# sirius1.net
KiCad netlist of a schematic drawn in EAGLE
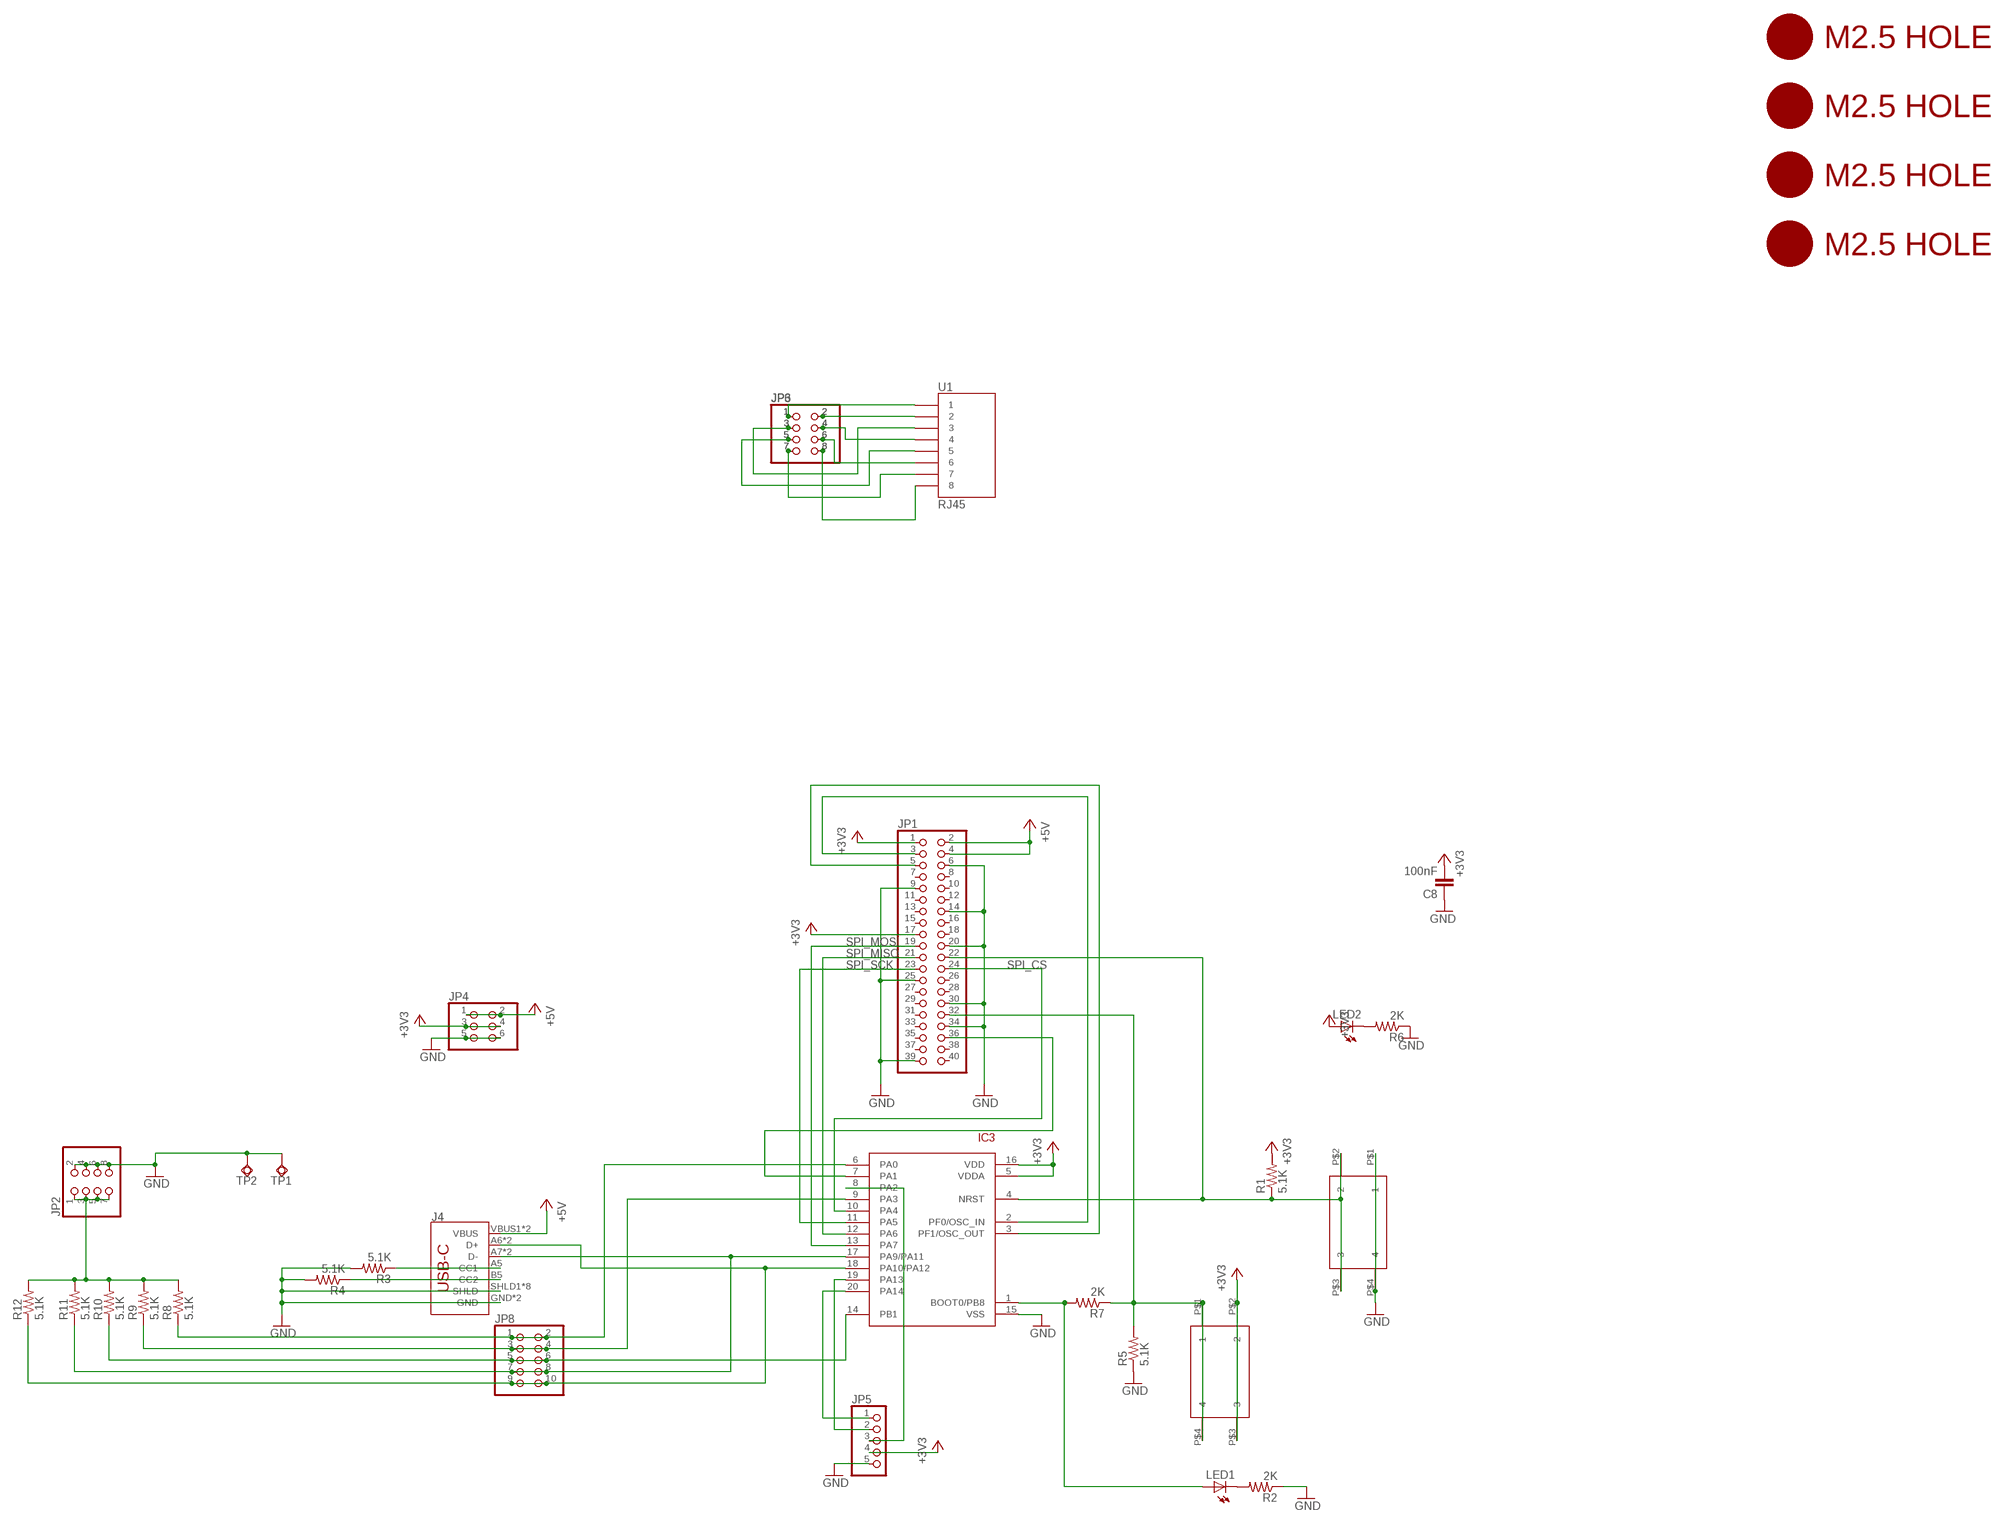
[diagram p0: schematic, sheet 1]

(export (version "E")
  (design (tool "Eeschema 10.0.6"))
  (components
    (comp (ref "C8")
      (value "100nF")
      (footprint "eagle-import:0805@1")
      (libsource (lib "eagle-import") (part "CAP0805"))
    )
    (comp (ref "IC3")
      (value "STM32F042F4")
      (footprint "eagle-import:TSSOP20")
      (libsource (lib "eagle-import") (part "STM32F042F4"))
    )
    (comp (ref "J4")
      (value "USB_C16PIN")
      (footprint "eagle-import:USB-C-16P")
      (libsource (lib "eagle-import") (part "USB_C16PIN"))
    )
    (comp (ref "JP1")
      (value "PINHD-2X20-BIG")
      (footprint "eagle-import:2X20-BIG")
      (libsource (lib "eagle-import") (part "PINHD-2X20-BIG"))
    )
    (comp (ref "JP2")
      (value "PINHD-2X4")
      (footprint "eagle-import:2X04")
      (libsource (lib "eagle-import") (part "PINHD-2X4"))
    )
    (comp (ref "JP3")
      (value "PINHD-2X4")
      (footprint "eagle-import:2X04")
      (libsource (lib "eagle-import") (part "PINHD-2X4"))
    )
    (comp (ref "JP4")
      (value "PINHD-2X3")
      (footprint "eagle-import:2X03")
      (libsource (lib "eagle-import") (part "PINHD-2X3"))
    )
    (comp (ref "JP5")
      (value "PINHD-1X5")
      (footprint "eagle-import:1X05")
      (libsource (lib "eagle-import") (part "PINHD-1X5"))
    )
    (comp (ref "JP6")
      (value "PINHD-2X4")
      (footprint "eagle-import:2X04")
      (libsource (lib "eagle-import") (part "PINHD-2X4"))
    )
    (comp (ref "JP8")
      (value "PINHD-2X5")
      (footprint "eagle-import:2X05")
      (libsource (lib "eagle-import") (part "PINHD-2X5"))
    )
    (comp (ref "LED1")
      (value "LEDCHIP-LED0805")
      (footprint "eagle-import:CHIP-LED0805")
      (libsource (lib "eagle-import") (part "LEDCHIP-LED0805"))
    )
    (comp (ref "LED2")
      (value "LEDCHIP-LED0805")
      (footprint "eagle-import:CHIP-LED0805")
      (libsource (lib "eagle-import") (part "LEDCHIP-LED0805"))
    )
    (comp (ref "R1")
      (value "5.1K")
      (footprint "eagle-import:0805")
      (libsource (lib "eagle-import") (part "RESISTOR0805-RES"))
    )
    (comp (ref "R2")
      (value "2K")
      (footprint "eagle-import:0805")
      (libsource (lib "eagle-import") (part "RESISTOR0805-RES"))
    )
    (comp (ref "R3")
      (value "5.1K")
      (footprint "eagle-import:0805")
      (libsource (lib "eagle-import") (part "RESISTOR0805-RES"))
    )
    (comp (ref "R4")
      (value "5.1K")
      (footprint "eagle-import:0805")
      (libsource (lib "eagle-import") (part "RESISTOR0805-RES"))
    )
    (comp (ref "R5")
      (value "5.1K")
      (footprint "eagle-import:0805")
      (libsource (lib "eagle-import") (part "RESISTOR0805-RES"))
    )
    (comp (ref "R6")
      (value "2K")
      (footprint "eagle-import:0805")
      (libsource (lib "eagle-import") (part "RESISTOR0805-RES"))
    )
    (comp (ref "R7")
      (value "2K")
      (footprint "eagle-import:0805")
      (libsource (lib "eagle-import") (part "RESISTOR0805-RES"))
    )
    (comp (ref "R8")
      (value "5.1K")
      (footprint "eagle-import:0805")
      (libsource (lib "eagle-import") (part "RESISTOR0805-RES"))
    )
    (comp (ref "R9")
      (value "5.1K")
      (footprint "eagle-import:0805")
      (libsource (lib "eagle-import") (part "RESISTOR0805-RES"))
    )
    (comp (ref "R10")
      (value "5.1K")
      (footprint "eagle-import:0805")
      (libsource (lib "eagle-import") (part "RESISTOR0805-RES"))
    )
    (comp (ref "R11")
      (value "5.1K")
      (footprint "eagle-import:0805")
      (libsource (lib "eagle-import") (part "RESISTOR0805-RES"))
    )
    (comp (ref "R12")
      (value "5.1K")
      (footprint "eagle-import:0805")
      (libsource (lib "eagle-import") (part "RESISTOR0805-RES"))
    )
    (comp (ref "SW1")
      (value "324_SW")
      (footprint "eagle-import:342_SWICH_FOOT")
      (libsource (lib "eagle-import") (part "324_SW"))
    )
    (comp (ref "SW4")
      (value "324_SW")
      (footprint "eagle-import:342_SWICH_FOOT")
      (libsource (lib "eagle-import") (part "324_SW"))
    )
    (comp (ref "TP1")
      (value "TPSQPAD1-20")
      (footprint "eagle-import:P1-20")
      (libsource (lib "eagle-import") (part "TPSQPAD1-20"))
    )
    (comp (ref "TP2")
      (value "TPSQPAD1-20")
      (footprint "eagle-import:P1-20")
      (libsource (lib "eagle-import") (part "TPSQPAD1-20"))
    )
    (comp (ref "U$2")
      (value "M2.5HOLE")
      (footprint "eagle-import:M2.5HOLE")
      (libsource (lib "eagle-import") (part "M2.5HOLE"))
    )
    (comp (ref "U$3")
      (value "M2.5HOLE")
      (footprint "eagle-import:M2.5HOLE")
      (libsource (lib "eagle-import") (part "M2.5HOLE"))
    )
    (comp (ref "U$4")
      (value "M2.5HOLE")
      (footprint "eagle-import:M2.5HOLE")
      (libsource (lib "eagle-import") (part "M2.5HOLE"))
    )
    (comp (ref "U$5")
      (value "M2.5HOLE")
      (footprint "eagle-import:M2.5HOLE")
      (libsource (lib "eagle-import") (part "M2.5HOLE"))
    )
    (comp (ref "U1")
      (value "RJ45")
      (footprint "eagle-import:RJ45-8")
      (libsource (lib "eagle-import") (part "RJ45-8PTH"))
    )
  )
  (nets
    (net (code "1") (name "+3V3") (class "Default")
      (node (ref "C8") (pin "2") (pinfunction "2_2") (pintype "passive"))
      (node (ref "IC3") (pin "16") (pinfunction "VDD_16") (pintype "bidirectional"))
      (node (ref "IC3") (pin "5") (pinfunction "VDDA_5") (pintype "bidirectional"))
      (node (ref "JP1") (pin "1") (pinfunction "1_1") (pintype "passive"))
      (node (ref "JP1") (pin "17") (pinfunction "17_17") (pintype "passive"))
      (node (ref "JP4") (pin "3") (pinfunction "3_3") (pintype "passive"))
      (node (ref "JP4") (pin "4") (pinfunction "4_4") (pintype "passive"))
      (node (ref "JP5") (pin "4") (pinfunction "4_4") (pintype "passive"))
      (node (ref "LED2") (pin "A") (pinfunction "A_A") (pintype "passive"))
      (node (ref "R1") (pin "2") (pinfunction "2_2") (pintype "passive"))
      (node (ref "SW1") (pin "P$2") (pinfunction "2_P$2") (pintype "bidirectional"))
      (node (ref "SW1") (pin "P$3") (pinfunction "3_P$3") (pintype "bidirectional"))
    )
    (net (code "2") (name "+5V") (class "Default")
      (node (ref "J4") (pin "VBUS1") (pinfunction "VBUS_VBUS1") (pintype "bidirectional"))
      (node (ref "J4") (pin "VBUS2") (pinfunction "VBUS_VBUS2") (pintype "bidirectional"))
      (node (ref "JP1") (pin "2") (pinfunction "2_2") (pintype "passive"))
      (node (ref "JP1") (pin "4") (pinfunction "4_4") (pintype "passive"))
      (node (ref "JP4") (pin "1") (pinfunction "1_1") (pintype "passive"))
      (node (ref "JP4") (pin "2") (pinfunction "2_2") (pintype "passive"))
    )
    (net (code "3") (name "/SPI_CS") (class "Default")
      (node (ref "IC3") (pin "10") (pinfunction "PA4_10") (pintype "bidirectional"))
      (node (ref "JP1") (pin "24") (pinfunction "24_24") (pintype "passive"))
    )
    (net (code "4") (name "/SPI_MISO") (class "Default")
      (node (ref "IC3") (pin "12") (pinfunction "PA6_12") (pintype "bidirectional"))
      (node (ref "JP1") (pin "21") (pinfunction "21_21") (pintype "passive"))
    )
    (net (code "5") (name "/SPI_MOSI") (class "Default")
      (node (ref "IC3") (pin "13") (pinfunction "PA7_13") (pintype "bidirectional"))
      (node (ref "JP1") (pin "19") (pinfunction "19_19") (pintype "passive"))
    )
    (net (code "6") (name "/SPI_SCK") (class "Default")
      (node (ref "IC3") (pin "11") (pinfunction "PA5_11") (pintype "bidirectional"))
      (node (ref "JP1") (pin "23") (pinfunction "23_23") (pintype "passive"))
    )
    (net (code "7") (name "GND") (class "Default")
      (node (ref "C8") (pin "1") (pinfunction "1_1") (pintype "passive"))
      (node (ref "IC3") (pin "15") (pinfunction "VSS_15") (pintype "bidirectional"))
      (node (ref "J4") (pin "GND") (pinfunction "GND_GND") (pintype "bidirectional"))
      (node (ref "J4") (pin "GND2") (pinfunction "GND_GND2") (pintype "bidirectional"))
      (node (ref "J4") (pin "SHLD1") (pinfunction "SHLD_SHLD1") (pintype "bidirectional"))
      (node (ref "J4") (pin "SHLD2") (pinfunction "SHLD_SHLD2") (pintype "bidirectional"))
      (node (ref "J4") (pin "SHLD3") (pinfunction "SHLD_SHLD3") (pintype "bidirectional"))
      (node (ref "J4") (pin "SHLD4") (pinfunction "SHLD_SHLD4") (pintype "bidirectional"))
      (node (ref "J4") (pin "SHLD5") (pinfunction "SHLD_SHLD5") (pintype "bidirectional"))
      (node (ref "J4") (pin "SHLD6") (pinfunction "SHLD_SHLD6") (pintype "bidirectional"))
      (node (ref "J4") (pin "SHLD7") (pinfunction "SHLD_SHLD7") (pintype "bidirectional"))
      (node (ref "J4") (pin "SHLD8") (pinfunction "SHLD_SHLD8") (pintype "bidirectional"))
      (node (ref "JP1") (pin "14") (pinfunction "14_14") (pintype "passive"))
      (node (ref "JP1") (pin "20") (pinfunction "20_20") (pintype "passive"))
      (node (ref "JP1") (pin "25") (pinfunction "25_25") (pintype "passive"))
      (node (ref "JP1") (pin "30") (pinfunction "30_30") (pintype "passive"))
      (node (ref "JP1") (pin "34") (pinfunction "34_34") (pintype "passive"))
      (node (ref "JP1") (pin "39") (pinfunction "39_39") (pintype "passive"))
      (node (ref "JP1") (pin "6") (pinfunction "6_6") (pintype "passive"))
      (node (ref "JP1") (pin "9") (pinfunction "9_9") (pintype "passive"))
      (node (ref "JP2") (pin "2") (pinfunction "2_2") (pintype "passive"))
      (node (ref "JP2") (pin "4") (pinfunction "4_4") (pintype "passive"))
      (node (ref "JP2") (pin "6") (pinfunction "6_6") (pintype "passive"))
      (node (ref "JP2") (pin "8") (pinfunction "8_8") (pintype "passive"))
      (node (ref "JP4") (pin "5") (pinfunction "5_5") (pintype "passive"))
      (node (ref "JP4") (pin "6") (pinfunction "6_6") (pintype "passive"))
      (node (ref "JP5") (pin "5") (pinfunction "5_5") (pintype "passive"))
      (node (ref "R2") (pin "1") (pinfunction "1_1") (pintype "passive"))
      (node (ref "R3") (pin "2") (pinfunction "2_2") (pintype "passive"))
      (node (ref "R4") (pin "2") (pinfunction "2_2") (pintype "passive"))
      (node (ref "R5") (pin "1") (pinfunction "1_1") (pintype "passive"))
      (node (ref "R6") (pin "1") (pinfunction "1_1") (pintype "passive"))
      (node (ref "SW4") (pin "P$1") (pinfunction "1_P$1") (pintype "bidirectional"))
      (node (ref "SW4") (pin "P$4") (pinfunction "4_P$4") (pintype "bidirectional"))
      (node (ref "TP1") (pin "TP") (pinfunction "TP_TP") (pintype "input"))
      (node (ref "TP2") (pin "TP") (pinfunction "TP_TP") (pintype "input"))
    )
    (net (code "8") (name "Net-(IC3-BOOT0{slash}PB8)") (class "Default")
      (node (ref "IC3") (pin "1") (pinfunction "BOOT0/PB8_1") (pintype "bidirectional"))
      (node (ref "LED1") (pin "A") (pinfunction "A_A") (pintype "passive"))
      (node (ref "R7") (pin "2") (pinfunction "2_2") (pintype "passive"))
    )
    (net (code "9") (name "Net-(IC3-NRST)") (class "Default")
      (node (ref "IC3") (pin "4") (pinfunction "NRST_4") (pintype "bidirectional"))
      (node (ref "JP1") (pin "22") (pinfunction "22_22") (pintype "passive"))
      (node (ref "R1") (pin "1") (pinfunction "1_1") (pintype "passive"))
      (node (ref "SW4") (pin "P$2") (pinfunction "2_P$2") (pintype "bidirectional"))
      (node (ref "SW4") (pin "P$3") (pinfunction "3_P$3") (pintype "bidirectional"))
    )
    (net (code "10") (name "Net-(IC3-PA0)") (class "Default")
      (node (ref "IC3") (pin "6") (pinfunction "PA0_6") (pintype "bidirectional"))
      (node (ref "JP8") (pin "1") (pinfunction "1_1") (pintype "passive"))
      (node (ref "JP8") (pin "2") (pinfunction "2_2") (pintype "passive"))
      (node (ref "R8") (pin "1") (pinfunction "1_1") (pintype "passive"))
    )
    (net (code "11") (name "Net-(IC3-PA1)") (class "Default")
      (node (ref "IC3") (pin "7") (pinfunction "PA1_7") (pintype "bidirectional"))
      (node (ref "JP1") (pin "36") (pinfunction "36_36") (pintype "passive"))
    )
    (net (code "12") (name "Net-(IC3-PA2)") (class "Default")
      (node (ref "IC3") (pin "8") (pinfunction "PA2_8") (pintype "bidirectional"))
      (node (ref "JP5") (pin "3") (pinfunction "3_3") (pintype "passive"))
    )
    (net (code "13") (name "Net-(IC3-PA3)") (class "Default")
      (node (ref "IC3") (pin "9") (pinfunction "PA3_9") (pintype "bidirectional"))
      (node (ref "JP8") (pin "3") (pinfunction "3_3") (pintype "passive"))
      (node (ref "JP8") (pin "4") (pinfunction "4_4") (pintype "passive"))
      (node (ref "R9") (pin "1") (pinfunction "1_1") (pintype "passive"))
    )
    (net (code "14") (name "Net-(IC3-PA9{slash}PA11)") (class "Default")
      (node (ref "IC3") (pin "17") (pinfunction "PA9/PA11_17") (pintype "bidirectional"))
      (node (ref "J4") (pin "A7") (pinfunction "D-_A7") (pintype "bidirectional"))
      (node (ref "J4") (pin "B7") (pinfunction "D-_B7") (pintype "bidirectional"))
      (node (ref "JP8") (pin "7") (pinfunction "7_7") (pintype "passive"))
      (node (ref "JP8") (pin "8") (pinfunction "8_8") (pintype "passive"))
      (node (ref "R11") (pin "1") (pinfunction "1_1") (pintype "passive"))
    )
    (net (code "15") (name "Net-(IC3-PA10{slash}PA12)") (class "Default")
      (node (ref "IC3") (pin "18") (pinfunction "PA10/PA12_18") (pintype "bidirectional"))
      (node (ref "J4") (pin "A6") (pinfunction "D+_A6") (pintype "bidirectional"))
      (node (ref "J4") (pin "B6") (pinfunction "D+_B6") (pintype "bidirectional"))
      (node (ref "JP8") (pin "10") (pinfunction "10_10") (pintype "passive"))
      (node (ref "JP8") (pin "9") (pinfunction "9_9") (pintype "passive"))
      (node (ref "R12") (pin "1") (pinfunction "1_1") (pintype "passive"))
    )
    (net (code "16") (name "Net-(IC3-PA13)") (class "Default")
      (node (ref "IC3") (pin "19") (pinfunction "PA13_19") (pintype "bidirectional"))
      (node (ref "JP5") (pin "2") (pinfunction "2_2") (pintype "passive"))
    )
    (net (code "17") (name "Net-(IC3-PA14)") (class "Default")
      (node (ref "IC3") (pin "20") (pinfunction "PA14_20") (pintype "bidirectional"))
      (node (ref "JP5") (pin "1") (pinfunction "1_1") (pintype "passive"))
    )
    (net (code "18") (name "Net-(IC3-PB1)") (class "Default")
      (node (ref "IC3") (pin "14") (pinfunction "PB1_14") (pintype "bidirectional"))
      (node (ref "JP8") (pin "5") (pinfunction "5_5") (pintype "passive"))
      (node (ref "JP8") (pin "6") (pinfunction "6_6") (pintype "passive"))
      (node (ref "R10") (pin "1") (pinfunction "1_1") (pintype "passive"))
    )
    (net (code "19") (name "Net-(IC3-PF0{slash}OSC_IN)") (class "Default")
      (node (ref "IC3") (pin "2") (pinfunction "PF0/OSC_IN_2") (pintype "bidirectional"))
      (node (ref "JP1") (pin "3") (pinfunction "3_3") (pintype "passive"))
    )
    (net (code "20") (name "Net-(IC3-PF1{slash}OSC_OUT)") (class "Default")
      (node (ref "IC3") (pin "3") (pinfunction "PF1/OSC_OUT_3") (pintype "bidirectional"))
      (node (ref "JP1") (pin "5") (pinfunction "5_5") (pintype "passive"))
    )
    (net (code "21") (name "Net-(J4-CC1)") (class "Default")
      (node (ref "J4") (pin "A5") (pinfunction "CC1_A5") (pintype "bidirectional"))
      (node (ref "R3") (pin "1") (pinfunction "1_1") (pintype "passive"))
    )
    (net (code "22") (name "Net-(J4-CC2)") (class "Default")
      (node (ref "J4") (pin "B5") (pinfunction "CC2_B5") (pintype "bidirectional"))
      (node (ref "R4") (pin "1") (pinfunction "1_1") (pintype "passive"))
    )
    (net (code "23") (name "Net-(JP2-Pad1)") (class "Default")
      (node (ref "JP2") (pin "1") (pinfunction "1_1") (pintype "passive"))
      (node (ref "JP2") (pin "3") (pinfunction "3_3") (pintype "passive"))
      (node (ref "JP2") (pin "5") (pinfunction "5_5") (pintype "passive"))
      (node (ref "JP2") (pin "7") (pinfunction "7_7") (pintype "passive"))
      (node (ref "R10") (pin "2") (pinfunction "2_2") (pintype "passive"))
      (node (ref "R11") (pin "2") (pinfunction "2_2") (pintype "passive"))
      (node (ref "R12") (pin "2") (pinfunction "2_2") (pintype "passive"))
      (node (ref "R8") (pin "2") (pinfunction "2_2") (pintype "passive"))
      (node (ref "R9") (pin "2") (pinfunction "2_2") (pintype "passive"))
    )
    (net (code "24") (name "Net-(JP3-Pad1)") (class "Default")
      (node (ref "JP3") (pin "1") (pinfunction "1_1") (pintype "passive"))
      (node (ref "JP6") (pin "1") (pinfunction "1_1") (pintype "passive"))
      (node (ref "U1") (pin "1") (pinfunction "1_1") (pintype "bidirectional"))
    )
    (net (code "25") (name "Net-(JP3-Pad2)") (class "Default")
      (node (ref "JP3") (pin "2") (pinfunction "2_2") (pintype "passive"))
      (node (ref "JP6") (pin "2") (pinfunction "2_2") (pintype "passive"))
      (node (ref "U1") (pin "2") (pinfunction "2_2") (pintype "bidirectional"))
    )
    (net (code "26") (name "Net-(JP3-Pad3)") (class "Default")
      (node (ref "JP3") (pin "3") (pinfunction "3_3") (pintype "passive"))
      (node (ref "JP6") (pin "3") (pinfunction "3_3") (pintype "passive"))
      (node (ref "U1") (pin "3") (pinfunction "3_3") (pintype "bidirectional"))
    )
    (net (code "27") (name "Net-(JP3-Pad4)") (class "Default")
      (node (ref "JP3") (pin "4") (pinfunction "4_4") (pintype "passive"))
      (node (ref "JP6") (pin "4") (pinfunction "4_4") (pintype "passive"))
      (node (ref "U1") (pin "4") (pinfunction "4_4") (pintype "bidirectional"))
    )
    (net (code "28") (name "Net-(JP3-Pad5)") (class "Default")
      (node (ref "JP3") (pin "5") (pinfunction "5_5") (pintype "passive"))
      (node (ref "JP6") (pin "5") (pinfunction "5_5") (pintype "passive"))
      (node (ref "U1") (pin "5") (pinfunction "5_5") (pintype "bidirectional"))
    )
    (net (code "29") (name "Net-(JP3-Pad6)") (class "Default")
      (node (ref "JP3") (pin "6") (pinfunction "6_6") (pintype "passive"))
      (node (ref "JP6") (pin "6") (pinfunction "6_6") (pintype "passive"))
      (node (ref "U1") (pin "6") (pinfunction "6_6") (pintype "bidirectional"))
    )
    (net (code "30") (name "Net-(JP3-Pad7)") (class "Default")
      (node (ref "JP3") (pin "7") (pinfunction "7_7") (pintype "passive"))
      (node (ref "JP6") (pin "7") (pinfunction "7_7") (pintype "passive"))
      (node (ref "U1") (pin "7") (pinfunction "7_7") (pintype "bidirectional"))
    )
    (net (code "31") (name "Net-(JP3-Pad8)") (class "Default")
      (node (ref "JP3") (pin "8") (pinfunction "8_8") (pintype "passive"))
      (node (ref "JP6") (pin "8") (pinfunction "8_8") (pintype "passive"))
      (node (ref "U1") (pin "8") (pinfunction "8_8") (pintype "bidirectional"))
    )
    (net (code "32") (name "Net-(LED1-PadC)") (class "Default")
      (node (ref "LED1") (pin "C") (pinfunction "C_C") (pintype "passive"))
      (node (ref "R2") (pin "2") (pinfunction "2_2") (pintype "passive"))
    )
    (net (code "33") (name "Net-(LED2-PadC)") (class "Default")
      (node (ref "LED2") (pin "C") (pinfunction "C_C") (pintype "passive"))
      (node (ref "R6") (pin "2") (pinfunction "2_2") (pintype "passive"))
    )
    (net (code "34") (name "Net-(SW1-1)") (class "Default")
      (node (ref "JP1") (pin "32") (pinfunction "32_32") (pintype "passive"))
      (node (ref "R5") (pin "2") (pinfunction "2_2") (pintype "passive"))
      (node (ref "R7") (pin "1") (pinfunction "1_1") (pintype "passive"))
      (node (ref "SW1") (pin "P$1") (pinfunction "1_P$1") (pintype "bidirectional"))
      (node (ref "SW1") (pin "P$4") (pinfunction "4_P$4") (pintype "bidirectional"))
    )
    (net (code "35") (name "unconnected-(JP1-Pad7)") (class "Default")
      (node (ref "JP1") (pin "7") (pinfunction "7_7") (pintype "passive"))
    )
    (net (code "36") (name "unconnected-(JP1-Pad8)") (class "Default")
      (node (ref "JP1") (pin "8") (pinfunction "8_8") (pintype "passive"))
    )
    (net (code "37") (name "unconnected-(JP1-Pad10)") (class "Default")
      (node (ref "JP1") (pin "10") (pinfunction "10_10") (pintype "passive"))
    )
    (net (code "38") (name "unconnected-(JP1-Pad11)") (class "Default")
      (node (ref "JP1") (pin "11") (pinfunction "11_11") (pintype "passive"))
    )
    (net (code "39") (name "unconnected-(JP1-Pad12)") (class "Default")
      (node (ref "JP1") (pin "12") (pinfunction "12_12") (pintype "passive"))
    )
    (net (code "40") (name "unconnected-(JP1-Pad13)") (class "Default")
      (node (ref "JP1") (pin "13") (pinfunction "13_13") (pintype "passive"))
    )
    (net (code "41") (name "unconnected-(JP1-Pad15)") (class "Default")
      (node (ref "JP1") (pin "15") (pinfunction "15_15") (pintype "passive"))
    )
    (net (code "42") (name "unconnected-(JP1-Pad16)") (class "Default")
      (node (ref "JP1") (pin "16") (pinfunction "16_16") (pintype "passive"))
    )
    (net (code "43") (name "unconnected-(JP1-Pad18)") (class "Default")
      (node (ref "JP1") (pin "18") (pinfunction "18_18") (pintype "passive"))
    )
    (net (code "44") (name "unconnected-(JP1-Pad26)") (class "Default")
      (node (ref "JP1") (pin "26") (pinfunction "26_26") (pintype "passive"))
    )
    (net (code "45") (name "unconnected-(JP1-Pad27)") (class "Default")
      (node (ref "JP1") (pin "27") (pinfunction "27_27") (pintype "passive"))
    )
    (net (code "46") (name "unconnected-(JP1-Pad28)") (class "Default")
      (node (ref "JP1") (pin "28") (pinfunction "28_28") (pintype "passive"))
    )
    (net (code "47") (name "unconnected-(JP1-Pad29)") (class "Default")
      (node (ref "JP1") (pin "29") (pinfunction "29_29") (pintype "passive"))
    )
    (net (code "48") (name "unconnected-(JP1-Pad31)") (class "Default")
      (node (ref "JP1") (pin "31") (pinfunction "31_31") (pintype "passive"))
    )
    (net (code "49") (name "unconnected-(JP1-Pad33)") (class "Default")
      (node (ref "JP1") (pin "33") (pinfunction "33_33") (pintype "passive"))
    )
    (net (code "50") (name "unconnected-(JP1-Pad35)") (class "Default")
      (node (ref "JP1") (pin "35") (pinfunction "35_35") (pintype "passive"))
    )
    (net (code "51") (name "unconnected-(JP1-Pad37)") (class "Default")
      (node (ref "JP1") (pin "37") (pinfunction "37_37") (pintype "passive"))
    )
    (net (code "52") (name "unconnected-(JP1-Pad38)") (class "Default")
      (node (ref "JP1") (pin "38") (pinfunction "38_38") (pintype "passive"))
    )
    (net (code "53") (name "unconnected-(JP1-Pad40)") (class "Default")
      (node (ref "JP1") (pin "40") (pinfunction "40_40") (pintype "passive"))
    )
  )
)
